# jrhahn_pico_pi_scale_cloudless__schemati.net
KiCad netlist of a schematic drawn in Altium Designer
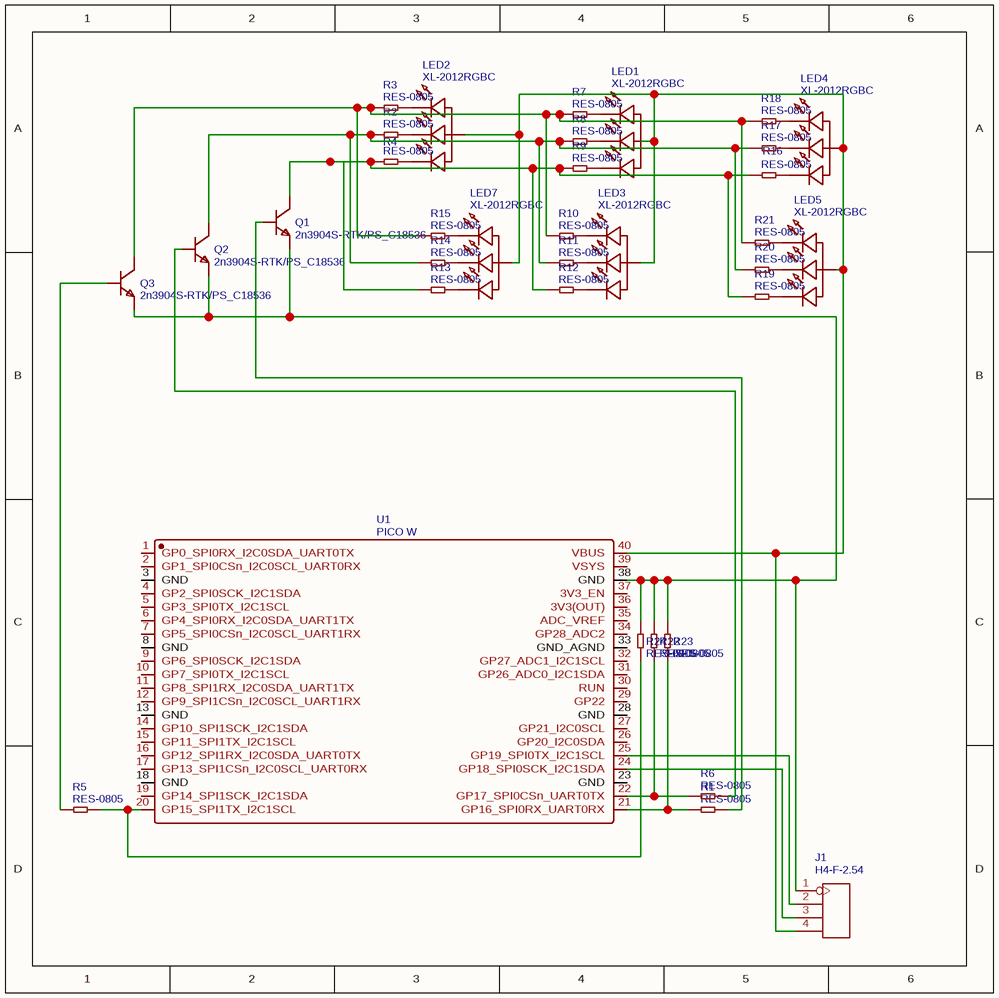
[diagram p0: jrhahn_pico_pi_scale_cloudless__schematics__Sheet_1_2024-02-07.schdoc]

(export (version "E")
  (design (tool "Eeschema 10.0.6"))
  (components
    (comp (ref "J1") (value "H4-F-2.54") (libsource (lib "altium-import") (part "root_0_H4-F-2.54_")))
    (comp (ref "LED1")
      (value "XL-2012RGBC")
      (fields (field (name "MANUFACTURER") "XINGLIGHT(成兴光)") (field (name "CONTRIBUTOR") "LCSC"))
      (libsource (lib "altium-import") (part "root_0_XL-2012RGBC_"))
    )
    (comp (ref "LED2")
      (value "XL-2012RGBC")
      (fields (field (name "MANUFACTURER") "XINGLIGHT(成兴光)") (field (name "CONTRIBUTOR") "LCSC"))
      (libsource (lib "altium-import") (part "root_0_XL-2012RGBC_"))
    )
    (comp (ref "LED3")
      (value "XL-2012RGBC")
      (fields (field (name "MANUFACTURER") "XINGLIGHT(成兴光)") (field (name "CONTRIBUTOR") "LCSC"))
      (libsource (lib "altium-import") (part "root_0_XL-2012RGBC_"))
    )
    (comp (ref "LED4")
      (value "XL-2012RGBC")
      (fields (field (name "MANUFACTURER") "XINGLIGHT(成兴光)") (field (name "CONTRIBUTOR") "LCSC"))
      (libsource (lib "altium-import") (part "root_0_XL-2012RGBC_"))
    )
    (comp (ref "LED5")
      (value "XL-2012RGBC")
      (fields (field (name "MANUFACTURER") "XINGLIGHT(成兴光)") (field (name "CONTRIBUTOR") "LCSC"))
      (libsource (lib "altium-import") (part "root_0_XL-2012RGBC_"))
    )
    (comp (ref "LED7")
      (value "XL-2012RGBC")
      (fields (field (name "MANUFACTURER") "XINGLIGHT(成兴光)") (field (name "CONTRIBUTOR") "LCSC"))
      (libsource (lib "altium-import") (part "root_0_XL-2012RGBC_"))
    )
    (comp (ref "Q1")
      (value "2n3904S-RTK/PS_C18536")
      (fields (field (name "MANUFACTURER") "KEC") (field (name "MANUFACTURER PART") "2N3904S-RTK/PS"))
      (libsource (lib "altium-import") (part "root_0_2n3904S-RTK/PS_C18536_"))
    )
    (comp (ref "Q2")
      (value "2n3904S-RTK/PS_C18536")
      (fields (field (name "MANUFACTURER") "KEC") (field (name "MANUFACTURER PART") "2N3904S-RTK/PS"))
      (libsource (lib "altium-import") (part "root_0_2n3904S-RTK/PS_C18536_"))
    )
    (comp (ref "Q3")
      (value "2n3904S-RTK/PS_C18536")
      (fields (field (name "MANUFACTURER") "KEC") (field (name "MANUFACTURER PART") "2N3904S-RTK/PS"))
      (libsource (lib "altium-import") (part "root_0_2n3904S-RTK/PS_C18536_"))
    )
    (comp (ref "R1") (value "RES-0805") (libsource (lib "altium-import") (part "root_0_RES-0805_")))
    (comp (ref "R2") (value "RES-0805") (libsource (lib "altium-import") (part "root_0_RES-0805_")))
    (comp (ref "R3") (value "RES-0805") (libsource (lib "altium-import") (part "root_0_RES-0805_")))
    (comp (ref "R4") (value "RES-0805") (libsource (lib "altium-import") (part "root_0_RES-0805_")))
    (comp (ref "R5") (value "RES-0805") (libsource (lib "altium-import") (part "root_0_RES-0805_")))
    (comp (ref "R6") (value "RES-0805") (libsource (lib "altium-import") (part "root_0_RES-0805_")))
    (comp (ref "R7") (value "RES-0805") (libsource (lib "altium-import") (part "root_0_RES-0805_")))
    (comp (ref "R8") (value "RES-0805") (libsource (lib "altium-import") (part "root_0_RES-0805_")))
    (comp (ref "R9") (value "RES-0805") (libsource (lib "altium-import") (part "root_0_RES-0805_")))
    (comp (ref "R10") (value "RES-0805") (libsource (lib "altium-import") (part "root_0_RES-0805_")))
    (comp (ref "R11") (value "RES-0805") (libsource (lib "altium-import") (part "root_0_RES-0805_")))
    (comp (ref "R12") (value "RES-0805") (libsource (lib "altium-import") (part "root_0_RES-0805_")))
    (comp (ref "R13") (value "RES-0805") (libsource (lib "altium-import") (part "root_0_RES-0805_")))
    (comp (ref "R14") (value "RES-0805") (libsource (lib "altium-import") (part "root_0_RES-0805_")))
    (comp (ref "R15") (value "RES-0805") (libsource (lib "altium-import") (part "root_0_RES-0805_")))
    (comp (ref "R16") (value "RES-0805") (libsource (lib "altium-import") (part "root_0_RES-0805_")))
    (comp (ref "R17") (value "RES-0805") (libsource (lib "altium-import") (part "root_0_RES-0805_")))
    (comp (ref "R18") (value "RES-0805") (libsource (lib "altium-import") (part "root_0_RES-0805_")))
    (comp (ref "R19") (value "RES-0805") (libsource (lib "altium-import") (part "root_0_RES-0805_")))
    (comp (ref "R20") (value "RES-0805") (libsource (lib "altium-import") (part "root_0_RES-0805_")))
    (comp (ref "R21") (value "RES-0805") (libsource (lib "altium-import") (part "root_0_RES-0805_")))
    (comp (ref "R22") (value "RES-0805") (libsource (lib "altium-import") (part "root_1_RES-0805_")))
    (comp (ref "R23") (value "RES-0805") (libsource (lib "altium-import") (part "root_1_RES-0805_")))
    (comp (ref "R24") (value "RES-0805") (libsource (lib "altium-import") (part "root_1_RES-0805_")))
    (comp (ref "U1")
      (value "PICO W")
      (fields (field (name "MANUFACTURER") "Raspberry Pi(树莓派)") (field (name "CONTRIBUTOR") "lcsc"))
      (libsource (lib "altium-import") (part "root_0_PICO W_"))
    )
  )
  (nets
    (net (code "1") (name "Net-(J1-P$1)") (class "Default")
      (node (ref "J1") (pin "1") (pinfunction "P$1_1") (pintype "passive"))
      (node (ref "Q1") (pin "1") (pinfunction "E_1") (pintype "passive"))
      (node (ref "Q2") (pin "1") (pinfunction "E_1") (pintype "passive"))
      (node (ref "Q3") (pin "1") (pinfunction "E_1") (pintype "passive"))
      (node (ref "R22") (pin "2") (pinfunction "2_2") (pintype "passive"))
      (node (ref "R23") (pin "2") (pinfunction "2_2") (pintype "passive"))
      (node (ref "R24") (pin "2") (pinfunction "2_2") (pintype "passive"))
      (node (ref "U1") (pin "38") (pinfunction "GND_38") (pintype "passive"))
    )
    (net (code "2") (name "Net-(J1-P$2)") (class "Default")
      (node (ref "J1") (pin "2") (pinfunction "P$2_2") (pintype "passive"))
      (node (ref "U1") (pin "25") (pinfunction "GP19_SPI0TX_I2C1SCL_25") (pintype "passive"))
    )
    (net (code "3") (name "Net-(J1-P$3)") (class "Default")
      (node (ref "J1") (pin "3") (pinfunction "P$3_3") (pintype "passive"))
      (node (ref "U1") (pin "24") (pinfunction "GP18_SPI0SCK_I2C1SDA_24") (pintype "passive"))
    )
    (net (code "4") (name "Net-(J1-P$4)") (class "Default")
      (node (ref "J1") (pin "4") (pinfunction "P$4_4") (pintype "passive"))
      (node (ref "LED1") (pin "3") (pinfunction "3_3") (pintype "passive"))
      (node (ref "LED2") (pin "3") (pinfunction "3_3") (pintype "passive"))
      (node (ref "LED3") (pin "3") (pinfunction "3_3") (pintype "passive"))
      (node (ref "LED4") (pin "3") (pinfunction "3_3") (pintype "passive"))
      (node (ref "LED5") (pin "3") (pinfunction "3_3") (pintype "passive"))
      (node (ref "LED7") (pin "3") (pinfunction "3_3") (pintype "passive"))
      (node (ref "U1") (pin "40") (pinfunction "VBUS_40") (pintype "passive"))
    )
    (net (code "5") (name "Net-(LED1-Pad1)") (class "Default")
      (node (ref "LED1") (pin "1") (pinfunction "1_1") (pintype "passive"))
      (node (ref "R7") (pin "2") (pinfunction "2_2") (pintype "passive"))
    )
    (net (code "6") (name "Net-(LED1-Pad2)") (class "Default")
      (node (ref "LED1") (pin "2") (pinfunction "2_2") (pintype "passive"))
      (node (ref "R8") (pin "2") (pinfunction "2_2") (pintype "passive"))
    )
    (net (code "7") (name "Net-(LED1-Pad4)") (class "Default")
      (node (ref "LED1") (pin "4") (pinfunction "4_4") (pintype "passive"))
      (node (ref "R9") (pin "2") (pinfunction "2_2") (pintype "passive"))
    )
    (net (code "8") (name "Net-(LED2-Pad1)") (class "Default")
      (node (ref "LED2") (pin "1") (pinfunction "1_1") (pintype "passive"))
      (node (ref "R3") (pin "2") (pinfunction "2_2") (pintype "passive"))
    )
    (net (code "9") (name "Net-(LED2-Pad2)") (class "Default")
      (node (ref "LED2") (pin "2") (pinfunction "2_2") (pintype "passive"))
      (node (ref "R2") (pin "2") (pinfunction "2_2") (pintype "passive"))
    )
    (net (code "10") (name "Net-(LED2-Pad4)") (class "Default")
      (node (ref "LED2") (pin "4") (pinfunction "4_4") (pintype "passive"))
      (node (ref "R4") (pin "2") (pinfunction "2_2") (pintype "passive"))
    )
    (net (code "11") (name "Net-(LED3-Pad1)") (class "Default")
      (node (ref "LED3") (pin "1") (pinfunction "1_1") (pintype "passive"))
      (node (ref "R10") (pin "2") (pinfunction "2_2") (pintype "passive"))
    )
    (net (code "12") (name "Net-(LED3-Pad2)") (class "Default")
      (node (ref "LED3") (pin "2") (pinfunction "2_2") (pintype "passive"))
      (node (ref "R11") (pin "2") (pinfunction "2_2") (pintype "passive"))
    )
    (net (code "13") (name "Net-(LED3-Pad4)") (class "Default")
      (node (ref "LED3") (pin "4") (pinfunction "4_4") (pintype "passive"))
      (node (ref "R12") (pin "2") (pinfunction "2_2") (pintype "passive"))
    )
    (net (code "14") (name "Net-(LED4-Pad1)") (class "Default")
      (node (ref "LED4") (pin "1") (pinfunction "1_1") (pintype "passive"))
      (node (ref "R18") (pin "2") (pinfunction "2_2") (pintype "passive"))
    )
    (net (code "15") (name "Net-(LED4-Pad2)") (class "Default")
      (node (ref "LED4") (pin "2") (pinfunction "2_2") (pintype "passive"))
      (node (ref "R17") (pin "2") (pinfunction "2_2") (pintype "passive"))
    )
    (net (code "16") (name "Net-(LED4-Pad4)") (class "Default")
      (node (ref "LED4") (pin "4") (pinfunction "4_4") (pintype "passive"))
      (node (ref "R16") (pin "2") (pinfunction "2_2") (pintype "passive"))
    )
    (net (code "17") (name "Net-(LED5-Pad1)") (class "Default")
      (node (ref "LED5") (pin "1") (pinfunction "1_1") (pintype "passive"))
      (node (ref "R21") (pin "2") (pinfunction "2_2") (pintype "passive"))
    )
    (net (code "18") (name "Net-(LED5-Pad2)") (class "Default")
      (node (ref "LED5") (pin "2") (pinfunction "2_2") (pintype "passive"))
      (node (ref "R20") (pin "2") (pinfunction "2_2") (pintype "passive"))
    )
    (net (code "19") (name "Net-(LED5-Pad4)") (class "Default")
      (node (ref "LED5") (pin "4") (pinfunction "4_4") (pintype "passive"))
      (node (ref "R19") (pin "2") (pinfunction "2_2") (pintype "passive"))
    )
    (net (code "20") (name "Net-(LED7-Pad1)") (class "Default")
      (node (ref "LED7") (pin "1") (pinfunction "1_1") (pintype "passive"))
      (node (ref "R15") (pin "2") (pinfunction "2_2") (pintype "passive"))
    )
    (net (code "21") (name "Net-(LED7-Pad2)") (class "Default")
      (node (ref "LED7") (pin "2") (pinfunction "2_2") (pintype "passive"))
      (node (ref "R14") (pin "2") (pinfunction "2_2") (pintype "passive"))
    )
    (net (code "22") (name "Net-(LED7-Pad4)") (class "Default")
      (node (ref "LED7") (pin "4") (pinfunction "4_4") (pintype "passive"))
      (node (ref "R13") (pin "2") (pinfunction "2_2") (pintype "passive"))
    )
    (net (code "23") (name "Net-(Q1-B)") (class "Default")
      (node (ref "Q1") (pin "2") (pinfunction "B_2") (pintype "passive"))
      (node (ref "R1") (pin "2") (pinfunction "2_2") (pintype "passive"))
    )
    (net (code "24") (name "Net-(Q1-C)") (class "Default")
      (node (ref "Q1") (pin "3") (pinfunction "C_3") (pintype "passive"))
      (node (ref "R12") (pin "1") (pinfunction "1_1") (pintype "passive"))
      (node (ref "R13") (pin "1") (pinfunction "1_1") (pintype "passive"))
      (node (ref "R16") (pin "1") (pinfunction "1_1") (pintype "passive"))
      (node (ref "R19") (pin "1") (pinfunction "1_1") (pintype "passive"))
      (node (ref "R4") (pin "1") (pinfunction "1_1") (pintype "passive"))
      (node (ref "R9") (pin "1") (pinfunction "1_1") (pintype "passive"))
    )
    (net (code "25") (name "Net-(Q2-B)") (class "Default")
      (node (ref "Q2") (pin "2") (pinfunction "B_2") (pintype "passive"))
      (node (ref "R6") (pin "2") (pinfunction "2_2") (pintype "passive"))
    )
    (net (code "26") (name "Net-(Q2-C)") (class "Default")
      (node (ref "Q2") (pin "3") (pinfunction "C_3") (pintype "passive"))
      (node (ref "R11") (pin "1") (pinfunction "1_1") (pintype "passive"))
      (node (ref "R14") (pin "1") (pinfunction "1_1") (pintype "passive"))
      (node (ref "R17") (pin "1") (pinfunction "1_1") (pintype "passive"))
      (node (ref "R2") (pin "1") (pinfunction "1_1") (pintype "passive"))
      (node (ref "R20") (pin "1") (pinfunction "1_1") (pintype "passive"))
      (node (ref "R8") (pin "1") (pinfunction "1_1") (pintype "passive"))
    )
    (net (code "27") (name "Net-(Q3-B)") (class "Default")
      (node (ref "Q3") (pin "2") (pinfunction "B_2") (pintype "passive"))
      (node (ref "R5") (pin "1") (pinfunction "1_1") (pintype "passive"))
    )
    (net (code "28") (name "Net-(Q3-C)") (class "Default")
      (node (ref "Q3") (pin "3") (pinfunction "C_3") (pintype "passive"))
      (node (ref "R10") (pin "1") (pinfunction "1_1") (pintype "passive"))
      (node (ref "R15") (pin "1") (pinfunction "1_1") (pintype "passive"))
      (node (ref "R18") (pin "1") (pinfunction "1_1") (pintype "passive"))
      (node (ref "R21") (pin "1") (pinfunction "1_1") (pintype "passive"))
      (node (ref "R3") (pin "1") (pinfunction "1_1") (pintype "passive"))
      (node (ref "R7") (pin "1") (pinfunction "1_1") (pintype "passive"))
    )
    (net (code "29") (name "Net-(U1-GP15_SPI1TX_I2C1SCL)") (class "Default")
      (node (ref "R24") (pin "1") (pinfunction "1_1") (pintype "passive"))
      (node (ref "R5") (pin "2") (pinfunction "2_2") (pintype "passive"))
      (node (ref "U1") (pin "20") (pinfunction "GP15_SPI1TX_I2C1SCL_20") (pintype "passive"))
    )
    (net (code "30") (name "Net-(U1-GP16_SPI0RX_UART0RX)") (class "Default")
      (node (ref "R1") (pin "1") (pinfunction "1_1") (pintype "passive"))
      (node (ref "R23") (pin "1") (pinfunction "1_1") (pintype "passive"))
      (node (ref "U1") (pin "21") (pinfunction "GP16_SPI0RX_UART0RX_21") (pintype "passive"))
    )
    (net (code "31") (name "Net-(U1-GP17_SPI0CSn_UART0TX)") (class "Default")
      (node (ref "R22") (pin "1") (pinfunction "1_1") (pintype "passive"))
      (node (ref "R6") (pin "1") (pinfunction "1_1") (pintype "passive"))
      (node (ref "U1") (pin "22") (pinfunction "GP17_SPI0CSn_UART0TX_22") (pintype "passive"))
    )
    (net (code "32") (name "unconnected-(U1-3V3(OUT)-Pad36)") (class "Default")
      (node (ref "U1") (pin "36") (pinfunction "3V3(OUT)_36") (pintype "passive"))
    )
    (net (code "33") (name "unconnected-(U1-3V3_EN-Pad37)") (class "Default")
      (node (ref "U1") (pin "37") (pinfunction "3V3_EN_37") (pintype "passive"))
    )
    (net (code "34") (name "unconnected-(U1-ADC_VREF-Pad35)") (class "Default")
      (node (ref "U1") (pin "35") (pinfunction "ADC_VREF_35") (pintype "passive"))
    )
    (net (code "35") (name "unconnected-(U1-GND-Pad3)") (class "Default")
      (node (ref "U1") (pin "3") (pinfunction "GND_3") (pintype "passive"))
    )
    (net (code "36") (name "unconnected-(U1-GND-Pad8)") (class "Default")
      (node (ref "U1") (pin "8") (pinfunction "GND_8") (pintype "passive"))
    )
    (net (code "37") (name "unconnected-(U1-GND-Pad13)") (class "Default")
      (node (ref "U1") (pin "13") (pinfunction "GND_13") (pintype "passive"))
    )
    (net (code "38") (name "unconnected-(U1-GND-Pad18)") (class "Default")
      (node (ref "U1") (pin "18") (pinfunction "GND_18") (pintype "passive"))
    )
    (net (code "39") (name "unconnected-(U1-GND-Pad23)") (class "Default")
      (node (ref "U1") (pin "23") (pinfunction "GND_23") (pintype "passive"))
    )
    (net (code "40") (name "unconnected-(U1-GND-Pad28)") (class "Default")
      (node (ref "U1") (pin "28") (pinfunction "GND_28") (pintype "passive"))
    )
    (net (code "41") (name "unconnected-(U1-GND_AGND-Pad33)") (class "Default")
      (node (ref "U1") (pin "33") (pinfunction "GND_AGND_33") (pintype "passive"))
    )
    (net (code "42") (name "unconnected-(U1-GP0_SPI0RX_I2C0SDA_UART0TX-Pad1)") (class "Default")
      (node (ref "U1") (pin "1") (pinfunction "GP0_SPI0RX_I2C0SDA_UART0TX_1") (pintype "passive"))
    )
    (net (code "43") (name "unconnected-(U1-GP1_SPI0CSn_I2C0SCL_UART0RX-Pad2)") (class "Default")
      (node (ref "U1") (pin "2") (pinfunction "GP1_SPI0CSn_I2C0SCL_UART0RX_2") (pintype "passive"))
    )
    (net (code "44") (name "unconnected-(U1-GP2_SPI0SCK_I2C1SDA-Pad4)") (class "Default")
      (node (ref "U1") (pin "4") (pinfunction "GP2_SPI0SCK_I2C1SDA_4") (pintype "passive"))
    )
    (net (code "45") (name "unconnected-(U1-GP3_SPI0TX_I2C1SCL-Pad5)") (class "Default")
      (node (ref "U1") (pin "5") (pinfunction "GP3_SPI0TX_I2C1SCL_5") (pintype "passive"))
    )
    (net (code "46") (name "unconnected-(U1-GP4_SPI0RX_I2C0SDA_UART1TX-Pad6)") (class "Default")
      (node (ref "U1") (pin "6") (pinfunction "GP4_SPI0RX_I2C0SDA_UART1TX_6") (pintype "passive"))
    )
    (net (code "47") (name "unconnected-(U1-GP5_SPI0CSn_I2C0SCL_UART1RX-Pad7)") (class "Default")
      (node (ref "U1") (pin "7") (pinfunction "GP5_SPI0CSn_I2C0SCL_UART1RX_7") (pintype "passive"))
    )
    (net (code "48") (name "unconnected-(U1-GP6_SPI0SCK_I2C1SDA-Pad9)") (class "Default")
      (node (ref "U1") (pin "9") (pinfunction "GP6_SPI0SCK_I2C1SDA_9") (pintype "passive"))
    )
    (net (code "49") (name "unconnected-(U1-GP7_SPI0TX_I2C1SCL-Pad10)") (class "Default")
      (node (ref "U1") (pin "10") (pinfunction "GP7_SPI0TX_I2C1SCL_10") (pintype "passive"))
    )
    (net (code "50") (name "unconnected-(U1-GP8_SPI1RX_I2C0SDA_UART1TX-Pad11)") (class "Default")
      (node (ref "U1") (pin "11") (pinfunction "GP8_SPI1RX_I2C0SDA_UART1TX_11") (pintype "passive"))
    )
    (net (code "51") (name "unconnected-(U1-GP9_SPI1CSn_I2C0SCL_UART1RX-Pad12)") (class "Default")
      (node (ref "U1") (pin "12") (pinfunction "GP9_SPI1CSn_I2C0SCL_UART1RX_12") (pintype "passive"))
    )
    (net (code "52") (name "unconnected-(U1-GP10_SPI1SCK_I2C1SDA-Pad14)") (class "Default")
      (node (ref "U1") (pin "14") (pinfunction "GP10_SPI1SCK_I2C1SDA_14") (pintype "passive"))
    )
    (net (code "53") (name "unconnected-(U1-GP11_SPI1TX_I2C1SCL-Pad15)") (class "Default")
      (node (ref "U1") (pin "15") (pinfunction "GP11_SPI1TX_I2C1SCL_15") (pintype "passive"))
    )
    (net (code "54") (name "unconnected-(U1-GP12_SPI1RX_I2C0SDA_UART0TX-Pad16)") (class "Default")
      (node (ref "U1") (pin "16") (pinfunction "GP12_SPI1RX_I2C0SDA_UART0TX_16") (pintype "passive"))
    )
    (net (code "55") (name "unconnected-(U1-GP13_SPI1CSn_I2C0SCL_UART0RX-Pad17)") (class "Default")
      (node (ref "U1") (pin "17") (pinfunction "GP13_SPI1CSn_I2C0SCL_UART0RX_17") (pintype "passive"))
    )
    (net (code "56") (name "unconnected-(U1-GP14_SPI1SCK_I2C1SDA-Pad19)") (class "Default")
      (node (ref "U1") (pin "19") (pinfunction "GP14_SPI1SCK_I2C1SDA_19") (pintype "passive"))
    )
    (net (code "57") (name "unconnected-(U1-GP20_I2C0SDA-Pad26)") (class "Default")
      (node (ref "U1") (pin "26") (pinfunction "GP20_I2C0SDA_26") (pintype "passive"))
    )
    (net (code "58") (name "unconnected-(U1-GP21_I2C0SCL-Pad27)") (class "Default")
      (node (ref "U1") (pin "27") (pinfunction "GP21_I2C0SCL_27") (pintype "passive"))
    )
    (net (code "59") (name "unconnected-(U1-GP22-Pad29)") (class "Default")
      (node (ref "U1") (pin "29") (pinfunction "GP22_29") (pintype "passive"))
    )
    (net (code "60") (name "unconnected-(U1-GP26_ADC0_I2C1SDA-Pad31)") (class "Default")
      (node (ref "U1") (pin "31") (pinfunction "GP26_ADC0_I2C1SDA_31") (pintype "passive"))
    )
    (net (code "61") (name "unconnected-(U1-GP27_ADC1_I2C1SCL-Pad32)") (class "Default")
      (node (ref "U1") (pin "32") (pinfunction "GP27_ADC1_I2C1SCL_32") (pintype "passive"))
    )
    (net (code "62") (name "unconnected-(U1-GP28_ADC2-Pad34)") (class "Default")
      (node (ref "U1") (pin "34") (pinfunction "GP28_ADC2_34") (pintype "passive"))
    )
    (net (code "63") (name "unconnected-(U1-RUN-Pad30)") (class "Default")
      (node (ref "U1") (pin "30") (pinfunction "RUN_30") (pintype "passive"))
    )
    (net (code "64") (name "unconnected-(U1-VSYS-Pad39)") (class "Default")
      (node (ref "U1") (pin "39") (pinfunction "VSYS_39") (pintype "passive"))
    )
  )
)
